# 4ButtonSwitch_ItsyBitsyM0_Rev1_0.net
KiCad netlist of a schematic drawn in EAGLE
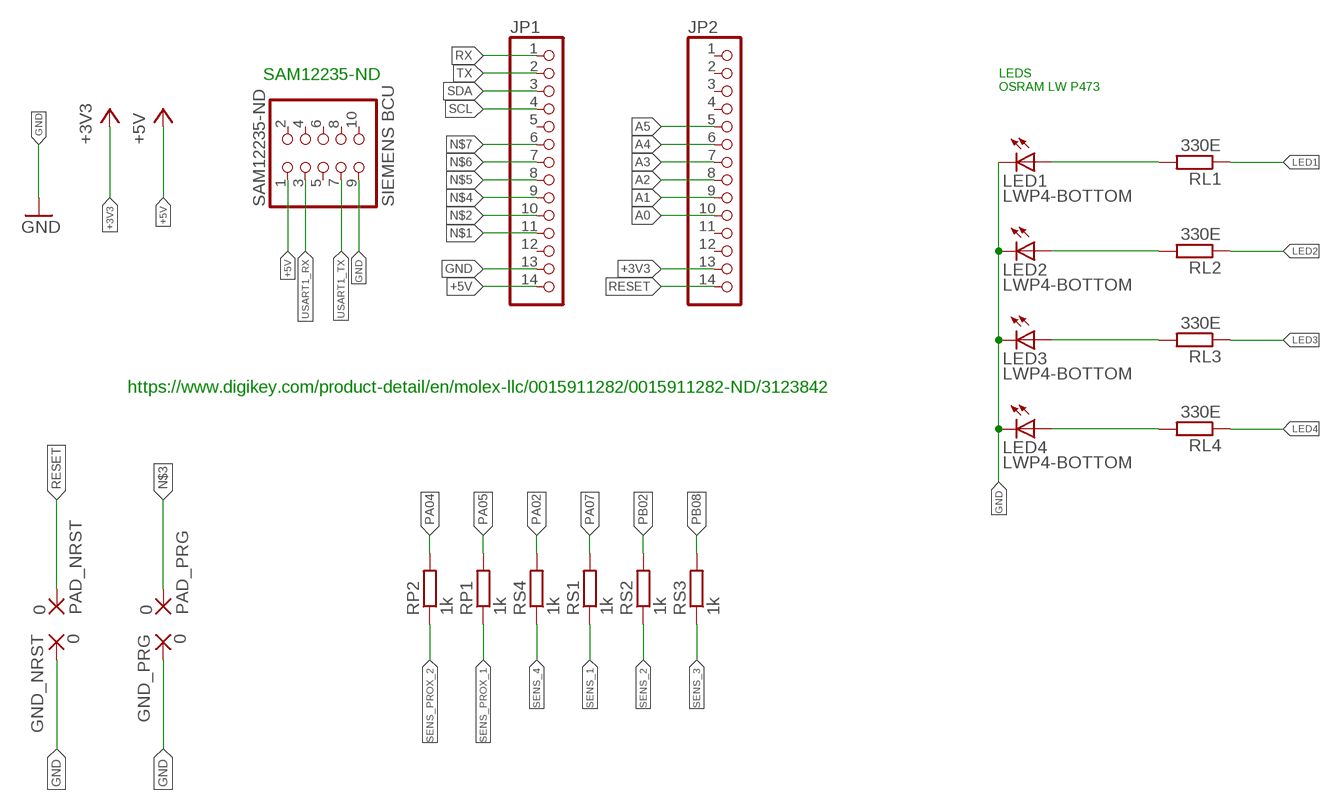
[diagram p0: schematic, sheet 1]

(export (version "E")
  (design (tool "Eeschema 10.0.6"))
  (components
    (comp (ref "GND_NRST")
      (value "0")
      (footprint "eagle-import:SMD2,54-5,08")
      (libsource (lib "eagle-import") (part "SMD5"))
    )
    (comp (ref "GND_PRG")
      (value "0")
      (footprint "eagle-import:SMD2,54-5,08")
      (libsource (lib "eagle-import") (part "SMD5"))
    )
    (comp (ref "JP1")
      (value "PINHD-1X141X14_SMT")
      (footprint "eagle-import:1X14_SMT")
      (libsource (lib "eagle-import") (part "PINHD-1X141X14_SMT"))
    )
    (comp (ref "JP2")
      (value "PINHD-1X141X14_SMT")
      (footprint "eagle-import:1X14_SMT")
      (libsource (lib "eagle-import") (part "PINHD-1X141X14_SMT"))
    )
    (comp (ref "LED1")
      (value "LWP4-BOTTOM")
      (footprint "eagle-import:P47F-BOTTOM")
      (libsource (lib "eagle-import") (part "P4-BOTTOMLW"))
    )
    (comp (ref "LED2")
      (value "LWP4-BOTTOM")
      (footprint "eagle-import:P47F-BOTTOM")
      (libsource (lib "eagle-import") (part "P4-BOTTOMLW"))
    )
    (comp (ref "LED3")
      (value "LWP4-BOTTOM")
      (footprint "eagle-import:P47F-BOTTOM")
      (libsource (lib "eagle-import") (part "P4-BOTTOMLW"))
    )
    (comp (ref "LED4")
      (value "LWP4-BOTTOM")
      (footprint "eagle-import:P47F-BOTTOM")
      (libsource (lib "eagle-import") (part "P4-BOTTOMLW"))
    )
    (comp (ref "PAD_NRST")
      (value "0")
      (footprint "eagle-import:SMD2,54-5,08")
      (libsource (lib "eagle-import") (part "SMD5"))
    )
    (comp (ref "PAD_PRG")
      (value "0")
      (footprint "eagle-import:SMD2,54-5,08")
      (libsource (lib "eagle-import") (part "SMD5"))
    )
    (comp (ref "RL1")
      (value "330E")
      (footprint "eagle-import:R1206")
      (libsource (lib "eagle-import") (part "R-EU_R1206"))
    )
    (comp (ref "RL2")
      (value "330E")
      (footprint "eagle-import:R1206")
      (libsource (lib "eagle-import") (part "R-EU_R1206"))
    )
    (comp (ref "RL3")
      (value "330E")
      (footprint "eagle-import:R1206")
      (libsource (lib "eagle-import") (part "R-EU_R1206"))
    )
    (comp (ref "RL4")
      (value "330E")
      (footprint "eagle-import:R1206")
      (libsource (lib "eagle-import") (part "R-EU_R1206"))
    )
    (comp (ref "RP1")
      (value "1k")
      (footprint "eagle-import:R1206")
      (libsource (lib "eagle-import") (part "R-EU_R1206"))
    )
    (comp (ref "RP2")
      (value "1k")
      (footprint "eagle-import:R1206")
      (libsource (lib "eagle-import") (part "R-EU_R1206"))
    )
    (comp (ref "RS1")
      (value "1k")
      (footprint "eagle-import:R1206")
      (libsource (lib "eagle-import") (part "R-EU_R1206"))
    )
    (comp (ref "RS2")
      (value "1k")
      (footprint "eagle-import:R1206")
      (libsource (lib "eagle-import") (part "R-EU_R1206"))
    )
    (comp (ref "RS3")
      (value "1k")
      (footprint "eagle-import:R1206")
      (libsource (lib "eagle-import") (part "R-EU_R1206"))
    )
    (comp (ref "RS4")
      (value "1k")
      (footprint "eagle-import:R1206")
      (libsource (lib "eagle-import") (part "R-EU_R1206"))
    )
    (comp (ref "SAM12235-ND")
      (value "SIEMENS BCU")
      (footprint "eagle-import:2X05SMD")
      (libsource (lib "eagle-import") (part "PINHD-2X5_2.54-SMD"))
    )
  )
  (nets
    (net (code "1") (name "+3V3") (class "Default")
      (node (ref "JP2") (pin "13") (pinfunction "13_13") (pintype "passive"))
    )
    (net (code "2") (name "+5V") (class "Default")
      (node (ref "JP1") (pin "14") (pinfunction "14_14") (pintype "passive"))
      (node (ref "SAM12235-ND") (pin "1") (pinfunction "1_1") (pintype "passive"))
    )
    (net (code "3") (name "A0") (class "Default")
      (node (ref "JP2") (pin "10") (pinfunction "10_10") (pintype "passive"))
    )
    (net (code "4") (name "A1") (class "Default")
      (node (ref "JP2") (pin "9") (pinfunction "9_9") (pintype "passive"))
    )
    (net (code "5") (name "A2") (class "Default")
      (node (ref "JP2") (pin "8") (pinfunction "8_8") (pintype "passive"))
    )
    (net (code "6") (name "A3") (class "Default")
      (node (ref "JP2") (pin "7") (pinfunction "7_7") (pintype "passive"))
    )
    (net (code "7") (name "A4") (class "Default")
      (node (ref "JP2") (pin "6") (pinfunction "6_6") (pintype "passive"))
    )
    (net (code "8") (name "A5") (class "Default")
      (node (ref "JP2") (pin "5") (pinfunction "5_5") (pintype "passive"))
    )
    (net (code "9") (name "GND") (class "Default")
      (node (ref "GND_NRST") (pin "1") (pinfunction "P_1") (pintype "passive"))
      (node (ref "GND_PRG") (pin "1") (pinfunction "P_1") (pintype "passive"))
      (node (ref "JP1") (pin "13") (pinfunction "13_13") (pintype "passive"))
      (node (ref "LED1") (pin "C") (pinfunction "C_C") (pintype "passive"))
      (node (ref "LED2") (pin "C") (pinfunction "C_C") (pintype "passive"))
      (node (ref "LED3") (pin "C") (pinfunction "C_C") (pintype "passive"))
      (node (ref "LED4") (pin "C") (pinfunction "C_C") (pintype "passive"))
      (node (ref "SAM12235-ND") (pin "9") (pinfunction "9_9") (pintype "passive"))
    )
    (net (code "10") (name "LED1") (class "Default")
      (node (ref "RL1") (pin "1") (pinfunction "1_1") (pintype "passive"))
    )
    (net (code "11") (name "LED2") (class "Default")
      (node (ref "RL2") (pin "1") (pinfunction "1_1") (pintype "passive"))
    )
    (net (code "12") (name "LED3") (class "Default")
      (node (ref "RL3") (pin "1") (pinfunction "1_1") (pintype "passive"))
    )
    (net (code "13") (name "LED4") (class "Default")
      (node (ref "RL4") (pin "1") (pinfunction "1_1") (pintype "passive"))
    )
    (net (code "14") (name "N$1") (class "Default")
      (node (ref "JP1") (pin "11") (pinfunction "11_11") (pintype "passive"))
    )
    (net (code "15") (name "N$2") (class "Default")
      (node (ref "JP1") (pin "10") (pinfunction "10_10") (pintype "passive"))
    )
    (net (code "16") (name "N$3") (class "Default")
      (node (ref "PAD_PRG") (pin "1") (pinfunction "P_1") (pintype "passive"))
    )
    (net (code "17") (name "N$4") (class "Default")
      (node (ref "JP1") (pin "9") (pinfunction "9_9") (pintype "passive"))
    )
    (net (code "18") (name "N$5") (class "Default")
      (node (ref "JP1") (pin "8") (pinfunction "8_8") (pintype "passive"))
    )
    (net (code "19") (name "N$6") (class "Default")
      (node (ref "JP1") (pin "7") (pinfunction "7_7") (pintype "passive"))
    )
    (net (code "20") (name "N$7") (class "Default")
      (node (ref "JP1") (pin "6") (pinfunction "6_6") (pintype "passive"))
    )
    (net (code "21") (name "Net-(LED1-PadA)") (class "Default")
      (node (ref "LED1") (pin "A") (pinfunction "A_A") (pintype "passive"))
      (node (ref "RL1") (pin "2") (pinfunction "2_2") (pintype "passive"))
    )
    (net (code "22") (name "Net-(LED2-PadA)") (class "Default")
      (node (ref "LED2") (pin "A") (pinfunction "A_A") (pintype "passive"))
      (node (ref "RL2") (pin "2") (pinfunction "2_2") (pintype "passive"))
    )
    (net (code "23") (name "Net-(LED3-PadA)") (class "Default")
      (node (ref "LED3") (pin "A") (pinfunction "A_A") (pintype "passive"))
      (node (ref "RL3") (pin "2") (pinfunction "2_2") (pintype "passive"))
    )
    (net (code "24") (name "Net-(LED4-PadA)") (class "Default")
      (node (ref "LED4") (pin "A") (pinfunction "A_A") (pintype "passive"))
      (node (ref "RL4") (pin "2") (pinfunction "2_2") (pintype "passive"))
    )
    (net (code "25") (name "PA02") (class "Default")
      (node (ref "RS4") (pin "2") (pinfunction "2_2") (pintype "passive"))
    )
    (net (code "26") (name "PA04") (class "Default")
      (node (ref "RP2") (pin "2") (pinfunction "2_2") (pintype "passive"))
    )
    (net (code "27") (name "PA05") (class "Default")
      (node (ref "RP1") (pin "2") (pinfunction "2_2") (pintype "passive"))
    )
    (net (code "28") (name "PA07") (class "Default")
      (node (ref "RS1") (pin "2") (pinfunction "2_2") (pintype "passive"))
    )
    (net (code "29") (name "PB02") (class "Default")
      (node (ref "RS2") (pin "2") (pinfunction "2_2") (pintype "passive"))
    )
    (net (code "30") (name "PB08") (class "Default")
      (node (ref "RS3") (pin "2") (pinfunction "2_2") (pintype "passive"))
    )
    (net (code "31") (name "RESET") (class "Default")
      (node (ref "JP2") (pin "14") (pinfunction "14_14") (pintype "passive"))
      (node (ref "PAD_NRST") (pin "1") (pinfunction "P_1") (pintype "passive"))
    )
    (net (code "32") (name "RX") (class "Default")
      (node (ref "JP1") (pin "1") (pinfunction "1_1") (pintype "passive"))
    )
    (net (code "33") (name "SCL") (class "Default")
      (node (ref "JP1") (pin "4") (pinfunction "4_4") (pintype "passive"))
    )
    (net (code "34") (name "SDA") (class "Default")
      (node (ref "JP1") (pin "3") (pinfunction "3_3") (pintype "passive"))
    )
    (net (code "35") (name "SENS_1") (class "Default")
      (node (ref "RS1") (pin "1") (pinfunction "1_1") (pintype "passive"))
    )
    (net (code "36") (name "SENS_2") (class "Default")
      (node (ref "RS2") (pin "1") (pinfunction "1_1") (pintype "passive"))
    )
    (net (code "37") (name "SENS_3") (class "Default")
      (node (ref "RS3") (pin "1") (pinfunction "1_1") (pintype "passive"))
    )
    (net (code "38") (name "SENS_4") (class "Default")
      (node (ref "RS4") (pin "1") (pinfunction "1_1") (pintype "passive"))
    )
    (net (code "39") (name "SENS_PROX_1") (class "Default")
      (node (ref "RP1") (pin "1") (pinfunction "1_1") (pintype "passive"))
    )
    (net (code "40") (name "SENS_PROX_2") (class "Default")
      (node (ref "RP2") (pin "1") (pinfunction "1_1") (pintype "passive"))
    )
    (net (code "41") (name "TX") (class "Default")
      (node (ref "JP1") (pin "2") (pinfunction "2_2") (pintype "passive"))
    )
    (net (code "42") (name "USART1_RX") (class "Default")
      (node (ref "SAM12235-ND") (pin "3") (pinfunction "3_3") (pintype "passive"))
    )
    (net (code "43") (name "USART1_TX") (class "Default")
      (node (ref "SAM12235-ND") (pin "7") (pinfunction "7_7") (pintype "passive"))
    )
    (net (code "44") (name "unconnected-(JP1-Pad5)") (class "Default")
      (node (ref "JP1") (pin "5") (pinfunction "5_5") (pintype "passive"))
    )
    (net (code "45") (name "unconnected-(JP1-Pad12)") (class "Default")
      (node (ref "JP1") (pin "12") (pinfunction "12_12") (pintype "passive"))
    )
    (net (code "46") (name "unconnected-(JP2-Pad1)") (class "Default")
      (node (ref "JP2") (pin "1") (pinfunction "1_1") (pintype "passive"))
    )
    (net (code "47") (name "unconnected-(JP2-Pad2)") (class "Default")
      (node (ref "JP2") (pin "2") (pinfunction "2_2") (pintype "passive"))
    )
    (net (code "48") (name "unconnected-(JP2-Pad3)") (class "Default")
      (node (ref "JP2") (pin "3") (pinfunction "3_3") (pintype "passive"))
    )
    (net (code "49") (name "unconnected-(JP2-Pad4)") (class "Default")
      (node (ref "JP2") (pin "4") (pinfunction "4_4") (pintype "passive"))
    )
    (net (code "50") (name "unconnected-(JP2-Pad11)") (class "Default")
      (node (ref "JP2") (pin "11") (pinfunction "11_11") (pintype "passive"))
    )
    (net (code "51") (name "unconnected-(JP2-Pad12)") (class "Default")
      (node (ref "JP2") (pin "12") (pinfunction "12_12") (pintype "passive"))
    )
    (net (code "52") (name "unconnected-(SAM12235-ND-Pad2)") (class "Default")
      (node (ref "SAM12235-ND") (pin "2") (pinfunction "2_2") (pintype "passive"))
    )
    (net (code "53") (name "unconnected-(SAM12235-ND-Pad4)") (class "Default")
      (node (ref "SAM12235-ND") (pin "4") (pinfunction "4_4") (pintype "passive"))
    )
    (net (code "54") (name "unconnected-(SAM12235-ND-Pad5)") (class "Default")
      (node (ref "SAM12235-ND") (pin "5") (pinfunction "5_5") (pintype "passive"))
    )
    (net (code "55") (name "unconnected-(SAM12235-ND-Pad6)") (class "Default")
      (node (ref "SAM12235-ND") (pin "6") (pinfunction "6_6") (pintype "passive"))
    )
    (net (code "56") (name "unconnected-(SAM12235-ND-Pad8)") (class "Default")
      (node (ref "SAM12235-ND") (pin "8") (pinfunction "8_8") (pintype "passive"))
    )
    (net (code "57") (name "unconnected-(SAM12235-ND-Pad10)") (class "Default")
      (node (ref "SAM12235-ND") (pin "10") (pinfunction "10_10") (pintype "passive"))
    )
  )
)
